# Sheet1.net
KiCad netlist of a schematic drawn in Altium Designer
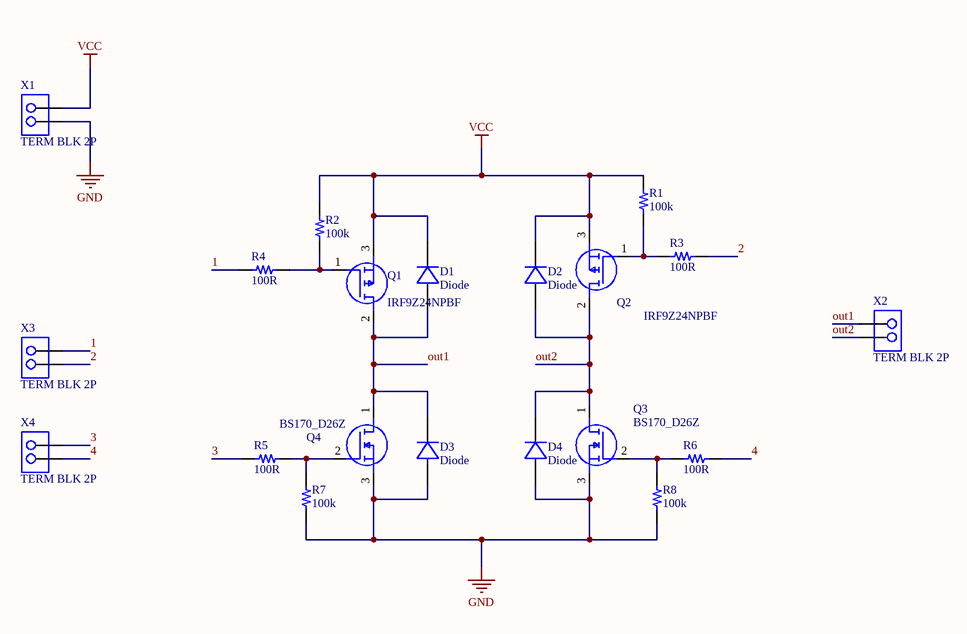
[diagram p0: Sheet1.SchDoc]

(export (version "E")
  (design (tool "Eeschema 10.0.6"))
  (components
    (comp (ref "D1")
      (value "Diode")
      (footprint "Diode DO_41")
      (libsource (lib "Default_Symbols") (part "Diode"))
    )
    (comp (ref "D2")
      (value "Diode")
      (footprint "Diode DO_41")
      (libsource (lib "Default_Symbols") (part "Diode"))
    )
    (comp (ref "D3")
      (value "Diode")
      (footprint "Diode DO_41")
      (libsource (lib "Default_Symbols") (part "Diode"))
    )
    (comp (ref "D4")
      (value "Diode")
      (footprint "Diode DO_41")
      (libsource (lib "Default_Symbols") (part "Diode"))
    )
    (comp (ref "Q1")
      (value "IRF9Z24NPBF")
      (footprint "SamacSys:TO254P469X1042X1967-3P")
      (description "MOSFET (P-Channel)")
      (fields (field (name "MOUSER PART NUMBER") "942-IRF9Z24NPBF"))
      (libsource (lib "*") (part "IRF9Z24NPBF"))
    )
    (comp (ref "Q2")
      (value "IRF9Z24NPBF")
      (footprint "SamacSys:TO254P469X1042X1967-3P")
      (description "MOSFET (P-Channel)")
      (fields (field (name "MOUSER PART NUMBER") "942-IRF9Z24NPBF"))
      (libsource (lib "*") (part "IRF9Z24NPBF"))
    )
    (comp (ref "Q3")
      (value "BS170_D26Z")
      (footprint "SamacSys:TO-92_FAIRCHILD")
      (description "MOSFET (N-Channel)")
      (fields (field (name "MOUSER PART NUMBER") "512-BS170D26Z"))
      (libsource (lib "*") (part "BS170_D26Z"))
    )
    (comp (ref "Q4")
      (value "BS170_D26Z")
      (footprint "SamacSys:TO-92_FAIRCHILD")
      (description "MOSFET (N-Channel)")
      (fields (field (name "MOUSER PART NUMBER") "512-BS170D26Z"))
      (libsource (lib "*") (part "BS170_D26Z"))
    )
    (comp (ref "R1")
      (value "100k")
      (footprint "Resistor THT")
      (description "1 kOhms ±5% 0.25W, 1/4W Through Hole Resistor Axial Flame Retardant Coating, Safety Carbon Film")
      (fields (field (name "MANIFACTURER PART NUMBER") "CF14JT1K00"))
      (libsource (lib "Default_Symbols") (part "Resistor THT"))
    )
    (comp (ref "R2")
      (value "100k")
      (footprint "Resistor THT")
      (description "1 kOhms ±5% 0.25W, 1/4W Through Hole Resistor Axial Flame Retardant Coating, Safety Carbon Film")
      (fields (field (name "MANIFACTURER PART NUMBER") "CF14JT1K00"))
      (libsource (lib "Default_Symbols") (part "Resistor THT"))
    )
    (comp (ref "R3")
      (value "100R")
      (footprint "Resistor THT")
      (description "1 kOhms ±5% 0.25W, 1/4W Through Hole Resistor Axial Flame Retardant Coating, Safety Carbon Film")
      (fields (field (name "MANIFACTURER PART NUMBER") "CF14JT1K00"))
      (libsource (lib "Default_Symbols") (part "Resistor THT"))
    )
    (comp (ref "R4")
      (value "100R")
      (footprint "Resistor THT")
      (description "1 kOhms ±5% 0.25W, 1/4W Through Hole Resistor Axial Flame Retardant Coating, Safety Carbon Film")
      (fields (field (name "MANIFACTURER PART NUMBER") "CF14JT1K00"))
      (libsource (lib "Default_Symbols") (part "Resistor THT"))
    )
    (comp (ref "R5")
      (value "100R")
      (footprint "Resistor THT")
      (description "1 kOhms ±5% 0.25W, 1/4W Through Hole Resistor Axial Flame Retardant Coating, Safety Carbon Film")
      (fields (field (name "MANIFACTURER PART NUMBER") "CF14JT1K00"))
      (libsource (lib "Default_Symbols") (part "Resistor THT"))
    )
    (comp (ref "R6")
      (value "100R")
      (footprint "Resistor THT")
      (description "1 kOhms ±5% 0.25W, 1/4W Through Hole Resistor Axial Flame Retardant Coating, Safety Carbon Film")
      (fields (field (name "MANIFACTURER PART NUMBER") "CF14JT1K00"))
      (libsource (lib "Default_Symbols") (part "Resistor THT"))
    )
    (comp (ref "R7")
      (value "100k")
      (footprint "Resistor THT")
      (description "1 kOhms ±5% 0.25W, 1/4W Through Hole Resistor Axial Flame Retardant Coating, Safety Carbon Film")
      (fields (field (name "MANIFACTURER PART NUMBER") "CF14JT1K00"))
      (libsource (lib "Default_Symbols") (part "Resistor THT"))
    )
    (comp (ref "R8")
      (value "100k")
      (footprint "Resistor THT")
      (description "1 kOhms ±5% 0.25W, 1/4W Through Hole Resistor Axial Flame Retardant Coating, Safety Carbon Film")
      (fields (field (name "MANIFACTURER PART NUMBER") "CF14JT1K00"))
      (libsource (lib "Default_Symbols") (part "Resistor THT"))
    )
    (comp (ref "X1")
      (value "TERM BLK 2P")
      (footprint "TERM BLK 2P")
      (description "TERM BLK 2P SIDE ENT 5.08MM PCB")
      (fields
        (field (name "MANUFACTURER") "Weidmüller")
        (field (name "MANUFACTURER PART NUMBER") "1760510000")
      )
      (libsource (lib "Default_Symbols") (part "TERM BLK 2P"))
    )
    (comp (ref "X2")
      (value "TERM BLK 2P")
      (footprint "TERM BLK 2P")
      (description "TERM BLK 2P SIDE ENT 5.08MM PCB")
      (fields
        (field (name "MANUFACTURER") "Weidmüller")
        (field (name "MANUFACTURER PART NUMBER") "1760510000")
      )
      (libsource (lib "Default_Symbols") (part "TERM BLK 2P"))
    )
    (comp (ref "X3")
      (value "TERM BLK 2P")
      (footprint "TERM BLK 2P")
      (description "TERM BLK 2P SIDE ENT 5.08MM PCB")
      (fields
        (field (name "MANUFACTURER") "Weidmüller")
        (field (name "MANUFACTURER PART NUMBER") "1760510000")
      )
      (libsource (lib "Default_Symbols") (part "TERM BLK 2P"))
    )
    (comp (ref "X4")
      (value "TERM BLK 2P")
      (footprint "TERM BLK 2P")
      (description "TERM BLK 2P SIDE ENT 5.08MM PCB")
      (fields
        (field (name "MANUFACTURER") "Weidmüller")
        (field (name "MANUFACTURER PART NUMBER") "1760510000")
      )
      (libsource (lib "Default_Symbols") (part "TERM BLK 2P"))
    )
  )
  (nets
    (net (code "1") (name "/1") (class "Default")
      (node (ref "R4") (pin "2") (pinfunction "2_2") (pintype "passive"))
      (node (ref "X3") (pin "0") (pinfunction "0_0") (pintype "passive"))
    )
    (net (code "2") (name "/2") (class "Default")
      (node (ref "R3") (pin "1") (pinfunction "1_1") (pintype "passive"))
      (node (ref "X3") (pin "1") (pinfunction "1_1") (pintype "passive"))
    )
    (net (code "3") (name "/3") (class "Default")
      (node (ref "R5") (pin "2") (pinfunction "2_2") (pintype "passive"))
      (node (ref "X4") (pin "0") (pinfunction "0_0") (pintype "passive"))
    )
    (net (code "4") (name "/4") (class "Default")
      (node (ref "R6") (pin "1") (pinfunction "1_1") (pintype "passive"))
      (node (ref "X4") (pin "1") (pinfunction "1_1") (pintype "passive"))
    )
    (net (code "5") (name "/out1") (class "Default")
      (node (ref "D1") (pin "8") (pinfunction "8_8") (pintype "passive"))
      (node (ref "D3") (pin "9") (pinfunction "9_9") (pintype "passive"))
      (node (ref "Q1") (pin "2") (pinfunction "D_2") (pintype "passive"))
      (node (ref "Q4") (pin "1") (pinfunction "D_1") (pintype "passive"))
      (node (ref "X2") (pin "1") (pinfunction "1_1") (pintype "passive"))
    )
    (net (code "6") (name "/out2") (class "Default")
      (node (ref "D2") (pin "8") (pinfunction "8_8") (pintype "passive"))
      (node (ref "D4") (pin "9") (pinfunction "9_9") (pintype "passive"))
      (node (ref "Q2") (pin "2") (pinfunction "D_2") (pintype "passive"))
      (node (ref "Q3") (pin "1") (pinfunction "D_1") (pintype "passive"))
      (node (ref "X2") (pin "0") (pinfunction "0_0") (pintype "passive"))
    )
    (net (code "7") (name "GND") (class "Default")
      (node (ref "D3") (pin "8") (pinfunction "8_8") (pintype "passive"))
      (node (ref "D4") (pin "8") (pinfunction "8_8") (pintype "passive"))
      (node (ref "Q3") (pin "3") (pinfunction "S_3") (pintype "passive"))
      (node (ref "Q4") (pin "3") (pinfunction "S_3") (pintype "passive"))
      (node (ref "R7") (pin "1") (pinfunction "1_1") (pintype "passive"))
      (node (ref "R8") (pin "1") (pinfunction "1_1") (pintype "passive"))
      (node (ref "X1") (pin "1") (pinfunction "1_1") (pintype "passive"))
    )
    (net (code "8") (name "Net-(Q1-G)") (class "Default")
      (node (ref "Q1") (pin "1") (pinfunction "G_1") (pintype "passive"))
      (node (ref "R2") (pin "1") (pinfunction "1_1") (pintype "passive"))
      (node (ref "R4") (pin "1") (pinfunction "1_1") (pintype "passive"))
    )
    (net (code "9") (name "Net-(Q2-G)") (class "Default")
      (node (ref "Q2") (pin "1") (pinfunction "G_1") (pintype "passive"))
      (node (ref "R1") (pin "1") (pinfunction "1_1") (pintype "passive"))
      (node (ref "R3") (pin "2") (pinfunction "2_2") (pintype "passive"))
    )
    (net (code "10") (name "Net-(Q3-G)") (class "Default")
      (node (ref "Q3") (pin "2") (pinfunction "G_2") (pintype "passive"))
      (node (ref "R6") (pin "2") (pinfunction "2_2") (pintype "passive"))
      (node (ref "R8") (pin "2") (pinfunction "2_2") (pintype "passive"))
    )
    (net (code "11") (name "Net-(Q4-G)") (class "Default")
      (node (ref "Q4") (pin "2") (pinfunction "G_2") (pintype "passive"))
      (node (ref "R5") (pin "1") (pinfunction "1_1") (pintype "passive"))
      (node (ref "R7") (pin "2") (pinfunction "2_2") (pintype "passive"))
    )
    (net (code "12") (name "VCC") (class "Default")
      (node (ref "D1") (pin "9") (pinfunction "9_9") (pintype "passive"))
      (node (ref "D2") (pin "9") (pinfunction "9_9") (pintype "passive"))
      (node (ref "Q1") (pin "3") (pinfunction "S_3") (pintype "passive"))
      (node (ref "Q2") (pin "3") (pinfunction "S_3") (pintype "passive"))
      (node (ref "R1") (pin "2") (pinfunction "2_2") (pintype "passive"))
      (node (ref "R2") (pin "2") (pinfunction "2_2") (pintype "passive"))
      (node (ref "X1") (pin "0") (pinfunction "0_0") (pintype "passive"))
    )
  )
)
